# mcu.net
KiCad netlist of a schematic drawn in Altium Designer
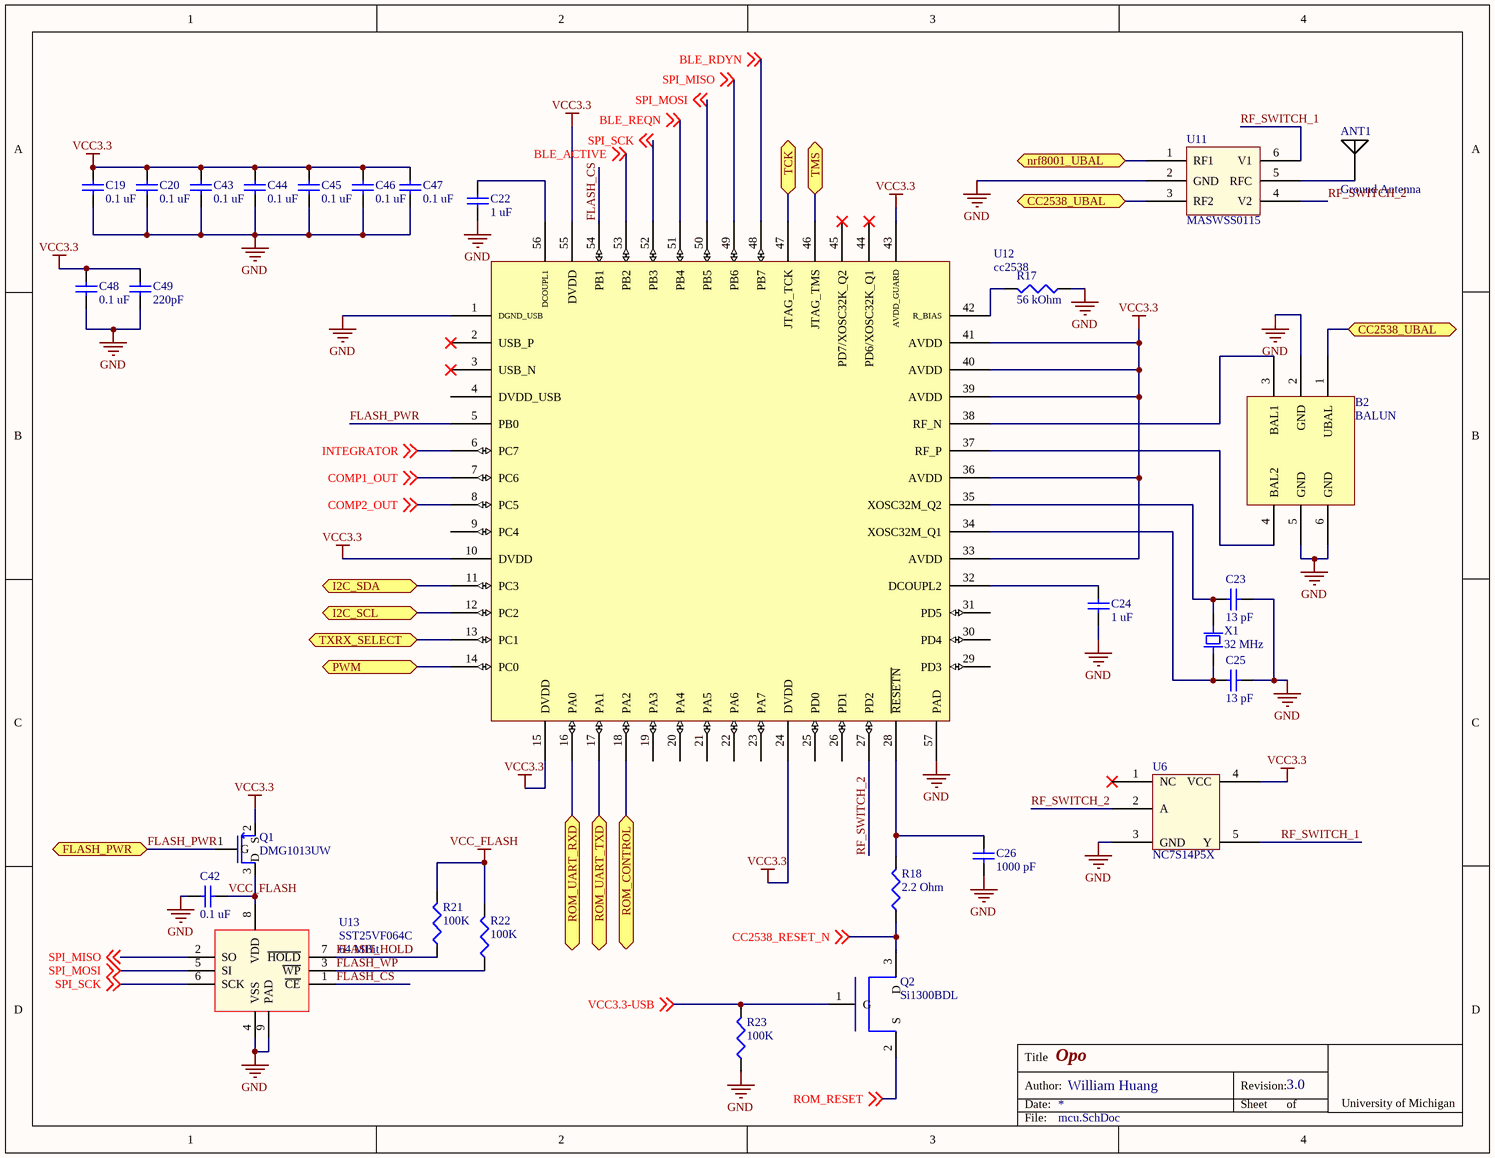
[diagram p0: mcu.SchDoc]

(export (version "E")
  (design (tool "Eeschema 10.0.6"))
  (components
    (comp (ref "ANT1")
      (value "Ground Antenna")
      (footprint "Chip Antenna")
      (description "2.4GHz Surface Mount Device (SMD) On Ground Antenna, 50 Ohms")
      (libsource (lib "opo_general") (part "Ground Antenna"))
    )
    (comp (ref "B2")
      (value "BALUN")
      (footprint "Chip Balun")
      (description "Johanson CC253X Balun")
      (libsource (lib "opo_general") (part "cc2538_Balun"))
    )
    (comp (ref "C19")
      (value "0.1 uF")
      (footprint "0402")
      (description "Ceramic capacitor, 0.1u, 0402 package")
      (fields (field (name "TOLERANCE") "10%") (field (name "Comment") "Ceramic capacitor"))
      (libsource (lib "rlc") (part "C_0.1u_0402_ceramic"))
    )
    (comp (ref "C20")
      (value "0.1 uF")
      (footprint "0402")
      (description "Ceramic capacitor, 0.1u, 0402 package")
      (fields (field (name "TOLERANCE") "10%") (field (name "Comment") "Ceramic capacitor"))
      (libsource (lib "rlc") (part "C_0.1u_0402_ceramic"))
    )
    (comp (ref "C22")
      (value "1 uF")
      (footprint "0402")
      (description "Ceramic capacitor, 1 uF, 0402 package")
      (fields (field (name "TOLERANCE") "10%") (field (name "Comment") "Ceramic capacitor"))
      (libsource (lib "rlc") (part "C_1u_0402_ceramic"))
    )
    (comp (ref "C23")
      (value "13 pF")
      (footprint "0402")
      (description "13pf, 50V, 2%, c0G, NP0, 0402, ceramic")
      (fields (field (name "MFR") "Murata") (field (name "MFR PART NUMBER") "GRM1555C1H130GA01D"))
      (libsource (lib "rlc") (part "C_13p_0402"))
    )
    (comp (ref "C24")
      (value "1 uF")
      (footprint "0402")
      (description "Ceramic capacitor, 1 uF, 0402 package")
      (fields (field (name "TOLERANCE") "10%") (field (name "Comment") "Ceramic capacitor"))
      (libsource (lib "rlc") (part "C_1u_0402_ceramic"))
    )
    (comp (ref "C25")
      (value "13 pF")
      (footprint "0402")
      (description "13pf, 50V, 2%, c0G, NP0, 0402, ceramic")
      (fields (field (name "MFR") "Murata") (field (name "MFR PART NUMBER") "GRM1555C1H130GA01D"))
      (libsource (lib "rlc") (part "C_13p_0402"))
    )
    (comp (ref "C26")
      (value "1000 pF")
      (footprint "0402")
      (description "Ceramic capacitor, 1000 pF, 0402 package")
      (fields (field (name "TOLERANCE") "10%") (field (name "Comment") "Ceramic capacitor"))
      (libsource (lib "rlc") (part "C_1000p_0402_ceramic"))
    )
    (comp (ref "C42")
      (value "0.1 uF")
      (footprint "0402")
      (description "Ceramic capacitor, 0.1u, 0402 package")
      (fields (field (name "TOLERANCE") "10%") (field (name "Comment") "Ceramic capacitor"))
      (libsource (lib "rlc") (part "C_0.1u_0402_ceramic"))
    )
    (comp (ref "C43")
      (value "0.1 uF")
      (footprint "0402")
      (description "Ceramic capacitor, 0.1u, 0402 package")
      (fields (field (name "TOLERANCE") "10%") (field (name "Comment") "Ceramic capacitor"))
      (libsource (lib "rlc") (part "C_0.1u_0402_ceramic"))
    )
    (comp (ref "C44")
      (value "0.1 uF")
      (footprint "0402")
      (description "Ceramic capacitor, 0.1u, 0402 package")
      (fields (field (name "TOLERANCE") "10%") (field (name "Comment") "Ceramic capacitor"))
      (libsource (lib "rlc") (part "C_0.1u_0402_ceramic"))
    )
    (comp (ref "C45")
      (value "0.1 uF")
      (footprint "0402")
      (description "Ceramic capacitor, 0.1u, 0402 package")
      (fields (field (name "TOLERANCE") "10%") (field (name "Comment") "Ceramic capacitor"))
      (libsource (lib "rlc") (part "C_0.1u_0402_ceramic"))
    )
    (comp (ref "C46")
      (value "0.1 uF")
      (footprint "0402")
      (description "Ceramic capacitor, 0.1u, 0402 package")
      (fields (field (name "TOLERANCE") "10%") (field (name "Comment") "Ceramic capacitor"))
      (libsource (lib "rlc") (part "C_0.1u_0402_ceramic"))
    )
    (comp (ref "C47")
      (value "0.1 uF")
      (footprint "0402")
      (description "Ceramic capacitor, 0.1u, 0402 package")
      (fields (field (name "TOLERANCE") "10%") (field (name "Comment") "Ceramic capacitor"))
      (libsource (lib "rlc") (part "C_0.1u_0402_ceramic"))
    )
    (comp (ref "C48")
      (value "0.1 uF")
      (footprint "0402")
      (description "Ceramic capacitor, 0.1u, 0402 package")
      (fields (field (name "TOLERANCE") "10%") (field (name "Comment") "Ceramic capacitor"))
      (libsource (lib "rlc") (part "C_0.1u_0402_ceramic"))
    )
    (comp (ref "C49")
      (value "220pF")
      (footprint "0402")
      (description "220pF 5% 50 V C0G NP0 0402 ceramic cap")
      (fields (field (name "MFR") "Murata") (field (name "MFR PART NUMBER") "GRM1555C1H221JA01D"))
      (libsource (lib "rlc") (part "C_220pf_0402_ceramic"))
    )
    (comp (ref "Q1")
      (value "DMG1013UW")
      (footprint "SC70-3")
      (description "P-CHANNEL ENHANCEMENT MODE MOSFET")
      (libsource (lib "opo_general") (part "DMG1013UW"))
    )
    (comp (ref "Q2")
      (value "Si1300BDL")
      (footprint "SC70-3")
      (description "MOSFET N-CH D-S 20V SC-70-3")
      (libsource (lib "opo_general") (part "Si1300BDL"))
    )
    (comp (ref "R17")
      (value "56 kOhm")
      (footprint "0402")
      (description "56 kOhm, 1%, .0603 W, 0402")
      (fields (field (name "MFR") "Rohm") (field (name "MFR PART NUMBER") "MCR01MRTF5602"))
      (libsource (lib "rlc") (part "R_56K_0402"))
    )
    (comp (ref "R18")
      (value "2.2 Ohm")
      (footprint "0402")
      (description "2.2 Ohm, 1%, .063W, 0402")
      (fields (field (name "MFR") "Vishay Dale") (field (name "MFR PART NUMBER") "CRCW04022R20FKED"))
      (libsource (lib "rlc") (part "R_2.2_0402"))
    )
    (comp (ref "R21")
      (value "100K")
      (footprint "0402")
      (description "Chip resistor, 100K, 0402 package")
      (fields (field (name "TOLERANCE") "1%") (field (name "POWER") "1/16 W"))
      (libsource (lib "rlc") (part "R_100K_0402"))
    )
    (comp (ref "R22")
      (value "100K")
      (footprint "0402")
      (description "Chip resistor, 100K, 0402 package")
      (fields (field (name "TOLERANCE") "1%") (field (name "POWER") "1/16 W"))
      (libsource (lib "rlc") (part "R_100K_0402"))
    )
    (comp (ref "R23")
      (value "100K")
      (footprint "0402")
      (description "Chip resistor, 100K, 0402 package")
      (fields (field (name "TOLERANCE") "1%") (field (name "POWER") "1/16 W"))
      (libsource (lib "rlc") (part "R_100K_0402"))
    )
    (comp (ref "U6")
      (value "NC7S14P5X")
      (footprint "SC70-5")
      (description "Single Inverter")
      (fields (field (name "MFR") "Fairchild"))
      (libsource (lib "opo_general") (part "NC7S14P5X"))
    )
    (comp (ref "U11")
      (value "MASWSS0115")
      (footprint "SC70-6")
      (description "Rf Switch")
      (fields (field (name "MFR") "M/A-Com") (field (name "MFR PART NUMBER") "MASWSS0115TR-3000"))
      (libsource (lib "opo_general") (part "MASWSS0115"))
    )
    (comp (ref "U12")
      (value "cc2538")
      (footprint "QFN50P800X800X100_HS-57N")
      (description "cc2538 MCU/802.15.4 radio")
      (libsource (lib "opo_general") (part "cc2538"))
    )
    (comp (ref "U13")
      (value "SST25VF064C")
      (footprint "WSON")
      (description "64 Mbit SPI Serial Dual I/O Flash")
      (fields (field (name "CAPACITY") "64 MBit"))
      (libsource (lib "opo_general") (part "SST25VF064C"))
    )
    (comp (ref "X1")
      (value "32 MHz")
      (footprint "FA-128")
      (description "32MHz, 10ppm, 10pF, 60 Ohm")
      (fields (field (name "MFR") "Epson") (field (name "MFR PART NUMBER") "FA-128 32.0000MF20X-K3"))
      (libsource (lib "opo_general") (part "X_32M_FA-128"))
    )
  )
  (nets
    (net (code "1") (name "/CC2538_UBAL") (class "Default")
      (node (ref "B2") (pin "1") (pinfunction "UBAL_1") (pintype "passive"))
      (node (ref "U11") (pin "3") (pinfunction "RF2_3") (pintype "passive"))
    )
    (net (code "2") (name "/FLASH_CS") (class "Default")
      (node (ref "U12") (pin "54") (pinfunction "PB1_54") (pintype "bidirectional"))
      (node (ref "U13") (pin "1") (pinfunction "~{CE}_1") (pintype "passive"))
    )
    (net (code "3") (name "/FLASH_HOLD") (class "Default")
      (node (ref "R21") (pin "2") (pintype "passive"))
      (node (ref "U13") (pin "7") (pinfunction "~{HOLD}_7") (pintype "passive"))
    )
    (net (code "4") (name "/FLASH_PWR") (class "Default")
      (node (ref "Q1") (pin "1") (pinfunction "G_1") (pintype "passive"))
      (node (ref "U12") (pin "5") (pinfunction "PB0_5") (pintype "passive"))
    )
    (net (code "5") (name "/FLASH_WP") (class "Default")
      (node (ref "R22") (pin "2") (pintype "passive"))
      (node (ref "U13") (pin "3") (pinfunction "~{WP}_3") (pintype "passive"))
    )
    (net (code "6") (name "/I2C_SCL") (class "Default")
      (node (ref "U12") (pin "12") (pinfunction "PC2_12") (pintype "bidirectional"))
    )
    (net (code "7") (name "/I2C_SDA") (class "Default")
      (node (ref "U12") (pin "11") (pinfunction "PC3_11") (pintype "bidirectional"))
    )
    (net (code "8") (name "/PWM") (class "Default")
      (node (ref "U12") (pin "14") (pinfunction "PC0_14") (pintype "bidirectional"))
    )
    (net (code "9") (name "/RF_SWITCH_1") (class "Default")
      (node (ref "U11") (pin "6") (pinfunction "V1_6") (pintype "passive"))
      (node (ref "U6") (pin "5") (pinfunction "Y_5") (pintype "passive"))
    )
    (net (code "10") (name "/RF_SWITCH_2") (class "Default")
      (node (ref "U11") (pin "4") (pinfunction "V2_4") (pintype "passive"))
      (node (ref "U12") (pin "27") (pinfunction "PD2_27") (pintype "bidirectional"))
      (node (ref "U6") (pin "2") (pinfunction "A_2") (pintype "passive"))
    )
    (net (code "11") (name "/ROM_CONTROL") (class "Default")
      (node (ref "U12") (pin "18") (pinfunction "PA2_18") (pintype "bidirectional"))
    )
    (net (code "12") (name "/ROM_UART_RXD") (class "Default")
      (node (ref "U12") (pin "16") (pinfunction "PA0_16") (pintype "bidirectional"))
    )
    (net (code "13") (name "/ROM_UART_TXD") (class "Default")
      (node (ref "U12") (pin "17") (pinfunction "PA1_17") (pintype "bidirectional"))
    )
    (net (code "14") (name "/TCK") (class "Default")
      (node (ref "U12") (pin "47") (pinfunction "JTAG_TCK_47") (pintype "passive"))
    )
    (net (code "15") (name "/TMS") (class "Default")
      (node (ref "U12") (pin "46") (pinfunction "JTAG_TMS_46") (pintype "passive"))
    )
    (net (code "16") (name "/TXRX_SELECT") (class "Default")
      (node (ref "U12") (pin "13") (pinfunction "PC1_13") (pintype "bidirectional"))
    )
    (net (code "17") (name "/nrf8001_UBAL") (class "Default")
      (node (ref "U11") (pin "1") (pinfunction "RF1_1") (pintype "passive"))
    )
    (net (code "18") (name "BLE_ACTIVE") (class "Default")
      (node (ref "U12") (pin "53") (pinfunction "PB2_53") (pintype "bidirectional"))
    )
    (net (code "19") (name "BLE_RDYN") (class "Default")
      (node (ref "U12") (pin "48") (pinfunction "PB7_48") (pintype "bidirectional"))
    )
    (net (code "20") (name "BLE_REQN") (class "Default")
      (node (ref "U12") (pin "51") (pinfunction "PB4_51") (pintype "bidirectional"))
    )
    (net (code "21") (name "CC2538_RESET_N") (class "Default")
      (node (ref "Q2") (pin "3") (pinfunction "D_3") (pintype "passive"))
      (node (ref "R18") (pin "2") (pintype "passive"))
    )
    (net (code "22") (name "COMP1_OUT") (class "Default")
      (node (ref "U12") (pin "7") (pinfunction "PC6_7") (pintype "bidirectional"))
    )
    (net (code "23") (name "COMP2_OUT") (class "Default")
      (node (ref "U12") (pin "8") (pinfunction "PC5_8") (pintype "bidirectional"))
    )
    (net (code "24") (name "GND") (class "Default")
      (node (ref "B2") (pin "2") (pinfunction "GND_2") (pintype "passive"))
      (node (ref "B2") (pin "5") (pinfunction "GND_5") (pintype "passive"))
      (node (ref "B2") (pin "6") (pinfunction "GND_6") (pintype "passive"))
      (node (ref "C19") (pin "2") (pintype "passive"))
      (node (ref "C20") (pin "2") (pintype "passive"))
      (node (ref "C22") (pin "2") (pintype "passive"))
      (node (ref "C23") (pin "2") (pintype "passive"))
      (node (ref "C24") (pin "2") (pintype "passive"))
      (node (ref "C25") (pin "1") (pintype "passive"))
      (node (ref "C26") (pin "2") (pintype "passive"))
      (node (ref "C42") (pin "1") (pintype "passive"))
      (node (ref "C43") (pin "2") (pintype "passive"))
      (node (ref "C44") (pin "2") (pintype "passive"))
      (node (ref "C45") (pin "2") (pintype "passive"))
      (node (ref "C46") (pin "2") (pintype "passive"))
      (node (ref "C47") (pin "2") (pintype "passive"))
      (node (ref "C48") (pin "2") (pintype "passive"))
      (node (ref "C49") (pin "2") (pintype "passive"))
      (node (ref "R17") (pin "2") (pintype "passive"))
      (node (ref "R23") (pin "2") (pintype "passive"))
      (node (ref "U11") (pin "2") (pinfunction "GND_2") (pintype "passive"))
      (node (ref "U12") (pin "1") (pinfunction "DGND_USB_1") (pintype "passive"))
      (node (ref "U12") (pin "57") (pinfunction "PAD_57") (pintype "passive"))
      (node (ref "U13") (pin "4") (pinfunction "VSS_4") (pintype "passive"))
      (node (ref "U13") (pin "9") (pinfunction "PAD_9") (pintype "passive"))
      (node (ref "U6") (pin "3") (pinfunction "GND_3") (pintype "passive"))
    )
    (net (code "25") (name "INTEGRATOR") (class "Default")
      (node (ref "U12") (pin "6") (pinfunction "PC7_6") (pintype "bidirectional"))
    )
    (net (code "26") (name "Net-(B2-BAL1)") (class "Default")
      (node (ref "B2") (pin "3") (pinfunction "BAL1_3") (pintype "passive"))
      (node (ref "U12") (pin "38") (pinfunction "RF_N_38") (pintype "passive"))
    )
    (net (code "27") (name "Net-(B2-BAL2)") (class "Default")
      (node (ref "B2") (pin "4") (pinfunction "BAL2_4") (pintype "passive"))
      (node (ref "U12") (pin "37") (pinfunction "RF_P_37") (pintype "passive"))
    )
    (net (code "28") (name "Net-(U11-RFC)") (class "Default")
      (node (ref "ANT1") (pin "1") (pintype "passive"))
      (node (ref "U11") (pin "5") (pinfunction "RFC_5") (pintype "passive"))
    )
    (net (code "29") (name "Net-(U12-DCOUPL1)") (class "Default")
      (node (ref "C22") (pin "1") (pintype "passive"))
      (node (ref "U12") (pin "56") (pinfunction "DCOUPL1_56") (pintype "power_in"))
    )
    (net (code "30") (name "Net-(U12-DCOUPL2)") (class "Default")
      (node (ref "C24") (pin "1") (pintype "passive"))
      (node (ref "U12") (pin "32") (pinfunction "DCOUPL2_32") (pintype "power_in"))
    )
    (net (code "31") (name "Net-(U12-R_BIAS)") (class "Default")
      (node (ref "R17") (pin "1") (pintype "passive"))
      (node (ref "U12") (pin "42") (pinfunction "R_BIAS_42") (pintype "passive"))
    )
    (net (code "32") (name "Net-(U12-XOSC32M_Q1)") (class "Default")
      (node (ref "C25") (pin "2") (pintype "passive"))
      (node (ref "U12") (pin "34") (pinfunction "XOSC32M_Q1_34") (pintype "passive"))
      (node (ref "X1") (pin "3") (pintype "passive"))
    )
    (net (code "33") (name "Net-(U12-XOSC32M_Q2)") (class "Default")
      (node (ref "C23") (pin "1") (pintype "passive"))
      (node (ref "U12") (pin "35") (pinfunction "XOSC32M_Q2_35") (pintype "passive"))
      (node (ref "X1") (pin "1") (pintype "passive"))
    )
    (net (code "34") (name "Net-(U12-~{RESETN})") (class "Default")
      (node (ref "C26") (pin "1") (pintype "passive"))
      (node (ref "R18") (pin "1") (pintype "passive"))
      (node (ref "U12") (pin "28") (pinfunction "~{RESETN}_28") (pintype "passive"))
    )
    (net (code "35") (name "ROM_RESET") (class "Default")
      (node (ref "Q2") (pin "2") (pinfunction "S_2") (pintype "passive"))
    )
    (net (code "36") (name "SPI_MISO") (class "Default")
      (node (ref "U12") (pin "49") (pinfunction "PB6_49") (pintype "bidirectional"))
      (node (ref "U13") (pin "2") (pinfunction "SO_2") (pintype "passive"))
    )
    (net (code "37") (name "SPI_MOSI") (class "Default")
      (node (ref "U12") (pin "50") (pinfunction "PB5_50") (pintype "bidirectional"))
      (node (ref "U13") (pin "5") (pinfunction "SI_5") (pintype "passive"))
    )
    (net (code "38") (name "SPI_SCK") (class "Default")
      (node (ref "U12") (pin "52") (pinfunction "PB3_52") (pintype "bidirectional"))
      (node (ref "U13") (pin "6") (pinfunction "SCK_6") (pintype "passive"))
    )
    (net (code "39") (name "VCC3.3") (class "Default")
      (node (ref "C19") (pin "1") (pintype "passive"))
      (node (ref "C20") (pin "1") (pintype "passive"))
      (node (ref "C43") (pin "1") (pintype "passive"))
      (node (ref "C44") (pin "1") (pintype "passive"))
      (node (ref "C45") (pin "1") (pintype "passive"))
      (node (ref "C46") (pin "1") (pintype "passive"))
      (node (ref "C47") (pin "1") (pintype "passive"))
      (node (ref "C48") (pin "1") (pintype "passive"))
      (node (ref "C49") (pin "1") (pintype "passive"))
      (node (ref "Q1") (pin "2") (pinfunction "S_2") (pintype "passive"))
      (node (ref "U12") (pin "10") (pinfunction "DVDD_10") (pintype "power_in"))
      (node (ref "U12") (pin "15") (pinfunction "DVDD_15") (pintype "power_in"))
      (node (ref "U12") (pin "24") (pinfunction "DVDD_24") (pintype "power_in"))
      (node (ref "U12") (pin "33") (pinfunction "AVDD_33") (pintype "power_in"))
      (node (ref "U12") (pin "36") (pinfunction "AVDD_36") (pintype "power_in"))
      (node (ref "U12") (pin "39") (pinfunction "AVDD_39") (pintype "power_in"))
      (node (ref "U12") (pin "40") (pinfunction "AVDD_40") (pintype "power_in"))
      (node (ref "U12") (pin "41") (pinfunction "AVDD_41") (pintype "power_in"))
      (node (ref "U12") (pin "43") (pinfunction "AVDD_GUARD_43") (pintype "power_in"))
      (node (ref "U12") (pin "55") (pinfunction "DVDD_55") (pintype "power_in"))
      (node (ref "U6") (pin "4") (pinfunction "VCC_4") (pintype "passive"))
    )
    (net (code "40") (name "VCC3.3-USB") (class "Default")
      (node (ref "Q2") (pin "1") (pinfunction "G_1") (pintype "passive"))
      (node (ref "R23") (pin "1") (pintype "passive"))
    )
    (net (code "41") (name "VCC_FLASH") (class "Default")
      (node (ref "C42") (pin "2") (pintype "passive"))
      (node (ref "Q1") (pin "3") (pinfunction "D_3") (pintype "passive"))
      (node (ref "R21") (pin "1") (pintype "passive"))
      (node (ref "R22") (pin "1") (pintype "passive"))
      (node (ref "U13") (pin "8") (pinfunction "VDD_8") (pintype "passive"))
    )
    (net (code "42") (name "unconnected-(U6-NC-Pad1)") (class "Default")
      (node (ref "U6") (pin "1") (pinfunction "NC_1") (pintype "passive+no_connect"))
    )
    (net (code "43") (name "unconnected-(U12-DVDD_USB-Pad4)") (class "Default")
      (node (ref "U12") (pin "4") (pinfunction "DVDD_USB_4") (pintype "passive"))
    )
    (net (code "44") (name "unconnected-(U12-PA3-Pad19)") (class "Default")
      (node (ref "U12") (pin "19") (pinfunction "PA3_19") (pintype "bidirectional"))
    )
    (net (code "45") (name "unconnected-(U12-PA4-Pad20)") (class "Default")
      (node (ref "U12") (pin "20") (pinfunction "PA4_20") (pintype "bidirectional"))
    )
    (net (code "46") (name "unconnected-(U12-PA5-Pad21)") (class "Default")
      (node (ref "U12") (pin "21") (pinfunction "PA5_21") (pintype "bidirectional"))
    )
    (net (code "47") (name "unconnected-(U12-PA6-Pad22)") (class "Default")
      (node (ref "U12") (pin "22") (pinfunction "PA6_22") (pintype "bidirectional"))
    )
    (net (code "48") (name "unconnected-(U12-PA7-Pad23)") (class "Default")
      (node (ref "U12") (pin "23") (pinfunction "PA7_23") (pintype "bidirectional"))
    )
    (net (code "49") (name "unconnected-(U12-PC4-Pad9)") (class "Default")
      (node (ref "U12") (pin "9") (pinfunction "PC4_9") (pintype "bidirectional"))
    )
    (net (code "50") (name "unconnected-(U12-PD0-Pad25)") (class "Default")
      (node (ref "U12") (pin "25") (pinfunction "PD0_25") (pintype "bidirectional"))
    )
    (net (code "51") (name "unconnected-(U12-PD1-Pad26)") (class "Default")
      (node (ref "U12") (pin "26") (pinfunction "PD1_26") (pintype "bidirectional"))
    )
    (net (code "52") (name "unconnected-(U12-PD3-Pad29)") (class "Default")
      (node (ref "U12") (pin "29") (pinfunction "PD3_29") (pintype "bidirectional"))
    )
    (net (code "53") (name "unconnected-(U12-PD4-Pad30)") (class "Default")
      (node (ref "U12") (pin "30") (pinfunction "PD4_30") (pintype "bidirectional"))
    )
    (net (code "54") (name "unconnected-(U12-PD5-Pad31)") (class "Default")
      (node (ref "U12") (pin "31") (pinfunction "PD5_31") (pintype "bidirectional"))
    )
    (net (code "55") (name "unconnected-(U12-PD6{slash}XOSC32K_Q1-Pad44)") (class "Default")
      (node (ref "U12") (pin "44") (pinfunction "PD6/XOSC32K_Q1_44") (pintype "passive+no_connect"))
    )
    (net (code "56") (name "unconnected-(U12-PD7{slash}XOSC32K_Q2-Pad45)") (class "Default")
      (node (ref "U12") (pin "45") (pinfunction "PD7/XOSC32K_Q2_45") (pintype "passive+no_connect"))
    )
    (net (code "57") (name "unconnected-(U12-USB_N-Pad3)") (class "Default")
      (node (ref "U12") (pin "3") (pinfunction "USB_N_3") (pintype "passive+no_connect"))
    )
    (net (code "58") (name "unconnected-(U12-USB_P-Pad2)") (class "Default")
      (node (ref "U12") (pin "2") (pinfunction "USB_P_2") (pintype "passive+no_connect"))
    )
  )
)
